# single_motor_driver_v6_patino.net
KiCad netlist of a schematic drawn in EAGLE
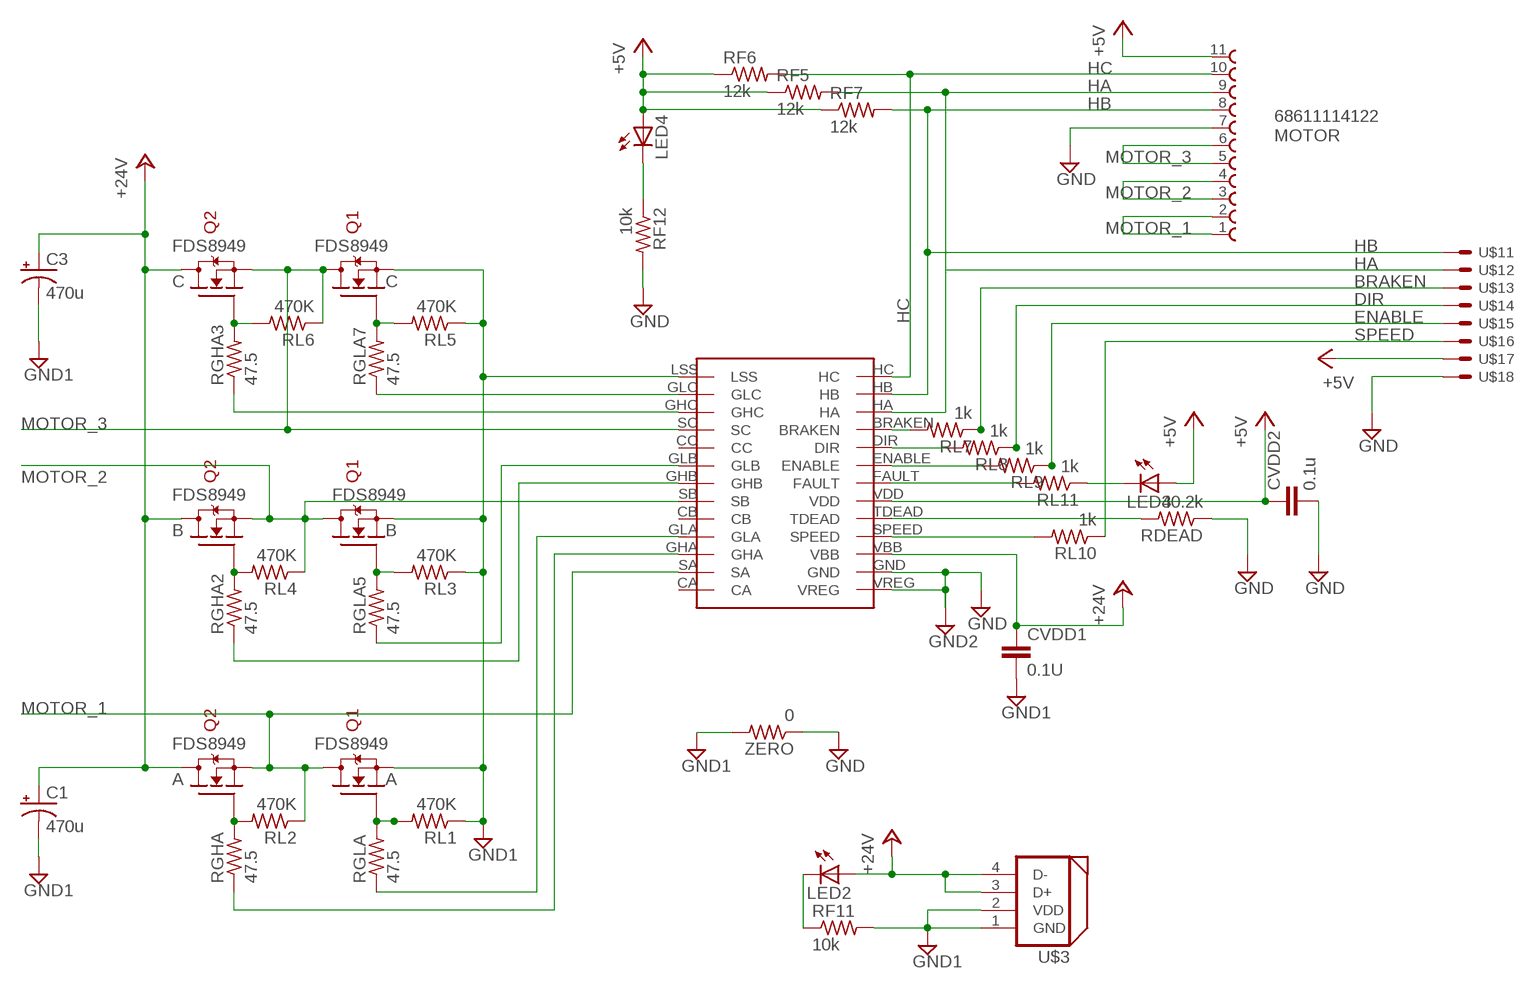
[diagram p0: schematic, sheet 1]

(export (version "E")
  (design (tool "Eeschema 10.0.6"))
  (components
    (comp (ref "A")
      (value "FDS8949")
      (footprint "eagle-import:SOIC8")
      (libsource (lib "eagle-import") (part "FDS8949"))
    )
    (comp (ref "B")
      (value "FDS8949")
      (footprint "eagle-import:SOIC8")
      (libsource (lib "eagle-import") (part "FDS8949"))
    )
    (comp (ref "C")
      (value "FDS8949")
      (footprint "eagle-import:SOIC8")
      (libsource (lib "eagle-import") (part "FDS8949"))
    )
    (comp (ref "C1")
      (value "470u")
      (footprint "eagle-import:140CLH-1010")
      (libsource (lib "eagle-import") (part "CPOL-US140CLH-1010"))
    )
    (comp (ref "C3")
      (value "470u")
      (footprint "eagle-import:140CLH-1010")
      (libsource (lib "eagle-import") (part "CPOL-US140CLH-1010"))
    )
    (comp (ref "CVDD1")
      (value "0.1U")
      (footprint "eagle-import:C0805")
      (libsource (lib "eagle-import") (part "C-EUC0805"))
    )
    (comp (ref "CVDD2")
      (value "0.1u")
      (footprint "eagle-import:C0805")
      (libsource (lib "eagle-import") (part "C-EUC0805"))
    )
    (comp (ref "LED2")
      (value "LEDCHIPLED_0805")
      (footprint "eagle-import:CHIPLED_0805")
      (libsource (lib "eagle-import") (part "LEDCHIPLED_0805"))
    )
    (comp (ref "LED3")
      (value "LEDCHIPLED_0805")
      (footprint "eagle-import:CHIPLED_0805")
      (libsource (lib "eagle-import") (part "LEDCHIPLED_0805"))
    )
    (comp (ref "LED4")
      (value "LEDCHIPLED_0805")
      (footprint "eagle-import:CHIPLED_0805")
      (libsource (lib "eagle-import") (part "LEDCHIPLED_0805"))
    )
    (comp (ref "MOTOR")
      (value "68611114122")
      (footprint "eagle-import:68611114122")
      (libsource (lib "eagle-import") (part "68611114122"))
    )
    (comp (ref "RDEAD")
      (value "40.2k")
      (footprint "eagle-import:R0805")
      (libsource (lib "eagle-import") (part "R-US_R0805"))
    )
    (comp (ref "RF5")
      (value "12k")
      (footprint "eagle-import:R0805")
      (libsource (lib "eagle-import") (part "R-US_R0805"))
    )
    (comp (ref "RF6")
      (value "12k")
      (footprint "eagle-import:R0805")
      (libsource (lib "eagle-import") (part "R-US_R0805"))
    )
    (comp (ref "RF7")
      (value "12k")
      (footprint "eagle-import:R0805")
      (libsource (lib "eagle-import") (part "R-US_R0805"))
    )
    (comp (ref "RF11")
      (value "10k")
      (footprint "eagle-import:R0805")
      (libsource (lib "eagle-import") (part "R-US_R0805"))
    )
    (comp (ref "RF12")
      (value "10k")
      (footprint "eagle-import:R0805")
      (libsource (lib "eagle-import") (part "R-US_R0805"))
    )
    (comp (ref "RGHA")
      (value "47.5")
      (footprint "eagle-import:R0805")
      (libsource (lib "eagle-import") (part "R-US_R0805"))
    )
    (comp (ref "RGHA2")
      (value "47.5")
      (footprint "eagle-import:R0805")
      (libsource (lib "eagle-import") (part "R-US_R0805"))
    )
    (comp (ref "RGHA3")
      (value "47.5")
      (footprint "eagle-import:R0805")
      (libsource (lib "eagle-import") (part "R-US_R0805"))
    )
    (comp (ref "RGLA")
      (value "47.5")
      (footprint "eagle-import:R0805")
      (libsource (lib "eagle-import") (part "R-US_R0805"))
    )
    (comp (ref "RGLA5")
      (value "47.5")
      (footprint "eagle-import:R0805")
      (libsource (lib "eagle-import") (part "R-US_R0805"))
    )
    (comp (ref "RGLA7")
      (value "47.5")
      (footprint "eagle-import:R0805")
      (libsource (lib "eagle-import") (part "R-US_R0805"))
    )
    (comp (ref "RL1")
      (value "470K")
      (footprint "eagle-import:R0805")
      (libsource (lib "eagle-import") (part "R-US_R0805"))
    )
    (comp (ref "RL2")
      (value "470K")
      (footprint "eagle-import:R0805")
      (libsource (lib "eagle-import") (part "R-US_R0805"))
    )
    (comp (ref "RL3")
      (value "470K")
      (footprint "eagle-import:R0805")
      (libsource (lib "eagle-import") (part "R-US_R0805"))
    )
    (comp (ref "RL4")
      (value "470K")
      (footprint "eagle-import:R0805")
      (libsource (lib "eagle-import") (part "R-US_R0805"))
    )
    (comp (ref "RL5")
      (value "470K")
      (footprint "eagle-import:R0805")
      (libsource (lib "eagle-import") (part "R-US_R0805"))
    )
    (comp (ref "RL6")
      (value "470K")
      (footprint "eagle-import:R0805")
      (libsource (lib "eagle-import") (part "R-US_R0805"))
    )
    (comp (ref "RL7")
      (value "1k")
      (footprint "eagle-import:R0805")
      (libsource (lib "eagle-import") (part "R-US_R0805"))
    )
    (comp (ref "RL8")
      (value "1k")
      (footprint "eagle-import:R0805")
      (libsource (lib "eagle-import") (part "R-US_R0805"))
    )
    (comp (ref "RL9")
      (value "1k")
      (footprint "eagle-import:R0805")
      (libsource (lib "eagle-import") (part "R-US_R0805"))
    )
    (comp (ref "RL10")
      (value "1k")
      (footprint "eagle-import:R0805")
      (libsource (lib "eagle-import") (part "R-US_R0805"))
    )
    (comp (ref "RL11")
      (value "1k")
      (footprint "eagle-import:R0805")
      (libsource (lib "eagle-import") (part "R-US_R0805"))
    )
    (comp (ref "U$1")
      (value "JST8")
      (footprint "eagle-import:JST")
      (libsource (lib "eagle-import") (part "JST8"))
    )
    (comp (ref "U$2")
      (value "TSSOP28-BRK")
      (footprint "eagle-import:TSSOP28-BRK")
      (libsource (lib "eagle-import") (part "TSSOP28-BRK"))
    )
    (comp (ref "U$3")
      (value "DYNAMIXEL_RS485")
      (footprint "eagle-import:DYNAMIXEL_SPOX_04")
      (libsource (lib "eagle-import") (part "DYNAMIXEL_RS485"))
    )
    (comp (ref "ZERO")
      (value "0")
      (footprint "eagle-import:R0805")
      (libsource (lib "eagle-import") (part "R-US_R0805"))
    )
  )
  (nets
    (net (code "1") (name "+5V") (class "Default")
      (node (ref "CVDD2") (pin "1") (pinfunction "1_1") (pintype "passive"))
      (node (ref "LED3") (pin "A") (pinfunction "A_A") (pintype "passive"))
      (node (ref "LED4") (pin "A") (pinfunction "A_A") (pintype "passive"))
      (node (ref "MOTOR") (pin "11") (pinfunction "11_11") (pintype "passive"))
      (node (ref "RF5") (pin "1") (pinfunction "1_1") (pintype "passive"))
      (node (ref "RF6") (pin "1") (pinfunction "1_1") (pintype "passive"))
      (node (ref "RF7") (pin "1") (pinfunction "1_1") (pintype "passive"))
      (node (ref "U$1") (pin "7") (pinfunction "S_7") (pintype "passive"))
      (node (ref "U$2") (pin "VDD") (pinfunction "VDD_VDD") (pintype "bidirectional"))
    )
    (net (code "2") (name "+24V") (class "Default")
      (node (ref "A") (pin "5") (pinfunction "D2_5") (pintype "passive"))
      (node (ref "A") (pin "6") (pinfunction "D2_6") (pintype "passive"))
      (node (ref "B") (pin "5") (pinfunction "D2_5") (pintype "passive"))
      (node (ref "B") (pin "6") (pinfunction "D2_6") (pintype "passive"))
      (node (ref "C") (pin "5") (pinfunction "D2_5") (pintype "passive"))
      (node (ref "C") (pin "6") (pinfunction "D2_6") (pintype "passive"))
      (node (ref "C1") (pin "+") (pinfunction "+_+") (pintype "passive"))
      (node (ref "C3") (pin "+") (pinfunction "+_+") (pintype "passive"))
      (node (ref "CVDD1") (pin "1") (pinfunction "1_1") (pintype "passive"))
      (node (ref "LED2") (pin "A") (pinfunction "A_A") (pintype "passive"))
      (node (ref "U$2") (pin "VBB") (pinfunction "VBB_VBB") (pintype "bidirectional"))
      (node (ref "U$3") (pin "3") (pinfunction "D+_3") (pintype "bidirectional"))
      (node (ref "U$3") (pin "4") (pinfunction "D-_4") (pintype "bidirectional"))
    )
    (net (code "3") (name "/BRAKEN") (class "Default")
      (node (ref "RL7") (pin "1") (pinfunction "1_1") (pintype "passive"))
      (node (ref "U$1") (pin "3") (pinfunction "S_3") (pintype "passive"))
    )
    (net (code "4") (name "/DIR") (class "Default")
      (node (ref "RL8") (pin "1") (pinfunction "1_1") (pintype "passive"))
      (node (ref "U$1") (pin "4") (pinfunction "S_4") (pintype "passive"))
    )
    (net (code "5") (name "/ENABLE") (class "Default")
      (node (ref "RL9") (pin "1") (pinfunction "1_1") (pintype "passive"))
      (node (ref "U$1") (pin "5") (pinfunction "S_5") (pintype "passive"))
    )
    (net (code "6") (name "/HA") (class "Default")
      (node (ref "MOTOR") (pin "9") (pinfunction "9_9") (pintype "passive"))
      (node (ref "RF5") (pin "2") (pinfunction "2_2") (pintype "passive"))
      (node (ref "U$1") (pin "2") (pinfunction "S_2") (pintype "passive"))
      (node (ref "U$2") (pin "HA") (pinfunction "HA_HA") (pintype "bidirectional"))
    )
    (net (code "7") (name "/HB") (class "Default")
      (node (ref "MOTOR") (pin "8") (pinfunction "8_8") (pintype "passive"))
      (node (ref "RF7") (pin "2") (pinfunction "2_2") (pintype "passive"))
      (node (ref "U$1") (pin "1") (pinfunction "S_1") (pintype "passive"))
      (node (ref "U$2") (pin "HB") (pinfunction "HB_HB") (pintype "bidirectional"))
    )
    (net (code "8") (name "/HC") (class "Default")
      (node (ref "MOTOR") (pin "10") (pinfunction "10_10") (pintype "passive"))
      (node (ref "RF6") (pin "2") (pinfunction "2_2") (pintype "passive"))
      (node (ref "U$2") (pin "HC") (pinfunction "HC_HC") (pintype "bidirectional"))
    )
    (net (code "9") (name "/MOTOR_1") (class "Default")
      (node (ref "A") (pin "3") (pinfunction "S2_3") (pintype "passive"))
      (node (ref "A") (pin "7") (pinfunction "D1_7") (pintype "passive"))
      (node (ref "A") (pin "8") (pinfunction "D1_8") (pintype "passive"))
      (node (ref "MOTOR") (pin "1") (pinfunction "1_1") (pintype "passive"))
      (node (ref "MOTOR") (pin "2") (pinfunction "2_2") (pintype "passive"))
      (node (ref "RL2") (pin "1") (pinfunction "1_1") (pintype "passive"))
      (node (ref "U$2") (pin "SA") (pinfunction "SA_SA") (pintype "bidirectional"))
    )
    (net (code "10") (name "/MOTOR_2") (class "Default")
      (node (ref "B") (pin "3") (pinfunction "S2_3") (pintype "passive"))
      (node (ref "B") (pin "7") (pinfunction "D1_7") (pintype "passive"))
      (node (ref "B") (pin "8") (pinfunction "D1_8") (pintype "passive"))
      (node (ref "MOTOR") (pin "3") (pinfunction "3_3") (pintype "passive"))
      (node (ref "MOTOR") (pin "4") (pinfunction "4_4") (pintype "passive"))
      (node (ref "RL4") (pin "1") (pinfunction "1_1") (pintype "passive"))
      (node (ref "U$2") (pin "SB") (pinfunction "SB_SB") (pintype "bidirectional"))
    )
    (net (code "11") (name "/MOTOR_3") (class "Default")
      (node (ref "C") (pin "3") (pinfunction "S2_3") (pintype "passive"))
      (node (ref "C") (pin "7") (pinfunction "D1_7") (pintype "passive"))
      (node (ref "C") (pin "8") (pinfunction "D1_8") (pintype "passive"))
      (node (ref "MOTOR") (pin "5") (pinfunction "5_5") (pintype "passive"))
      (node (ref "MOTOR") (pin "6") (pinfunction "6_6") (pintype "passive"))
      (node (ref "RL6") (pin "1") (pinfunction "1_1") (pintype "passive"))
      (node (ref "U$2") (pin "SC") (pinfunction "SC_SC") (pintype "bidirectional"))
    )
    (net (code "12") (name "/SPEED") (class "Default")
      (node (ref "RL10") (pin "1") (pinfunction "1_1") (pintype "passive"))
      (node (ref "U$1") (pin "6") (pinfunction "S_6") (pintype "passive"))
    )
    (net (code "13") (name "GND") (class "Default")
      (node (ref "CVDD2") (pin "2") (pinfunction "2_2") (pintype "passive"))
      (node (ref "MOTOR") (pin "7") (pinfunction "7_7") (pintype "passive"))
      (node (ref "RDEAD") (pin "1") (pinfunction "1_1") (pintype "passive"))
      (node (ref "RF12") (pin "2") (pinfunction "2_2") (pintype "passive"))
      (node (ref "U$1") (pin "8") (pinfunction "S_8") (pintype "passive"))
      (node (ref "U$2") (pin "GND") (pinfunction "GND_GND") (pintype "bidirectional"))
      (node (ref "U$2") (pin "VREG") (pinfunction "VREG_VREG") (pintype "bidirectional"))
      (node (ref "ZERO") (pin "1") (pinfunction "1_1") (pintype "passive"))
    )
    (net (code "14") (name "GND1") (class "Default")
      (node (ref "A") (pin "1") (pinfunction "S1_1") (pintype "passive"))
      (node (ref "B") (pin "1") (pinfunction "S1_1") (pintype "passive"))
      (node (ref "C") (pin "1") (pinfunction "S1_1") (pintype "passive"))
      (node (ref "C1") (pin "-") (pinfunction "-_-") (pintype "passive"))
      (node (ref "C3") (pin "-") (pinfunction "-_-") (pintype "passive"))
      (node (ref "CVDD1") (pin "2") (pinfunction "2_2") (pintype "passive"))
      (node (ref "RF11") (pin "2") (pinfunction "2_2") (pintype "passive"))
      (node (ref "RL1") (pin "1") (pinfunction "1_1") (pintype "passive"))
      (node (ref "RL3") (pin "1") (pinfunction "1_1") (pintype "passive"))
      (node (ref "RL5") (pin "1") (pinfunction "1_1") (pintype "passive"))
      (node (ref "U$2") (pin "LSS") (pinfunction "LSS_LSS") (pintype "bidirectional"))
      (node (ref "U$3") (pin "1") (pinfunction "GND_1") (pintype "power_in"))
      (node (ref "U$3") (pin "2") (pinfunction "VDD_2") (pintype "power_in"))
      (node (ref "ZERO") (pin "2") (pinfunction "2_2") (pintype "passive"))
    )
    (net (code "15") (name "Net-(A-G1)") (class "Default")
      (node (ref "A") (pin "2") (pinfunction "G1_2") (pintype "passive"))
      (node (ref "RGLA") (pin "2") (pinfunction "2_2") (pintype "passive"))
      (node (ref "RL1") (pin "2") (pinfunction "2_2") (pintype "passive"))
    )
    (net (code "16") (name "Net-(A-G2)") (class "Default")
      (node (ref "A") (pin "4") (pinfunction "G2_4") (pintype "passive"))
      (node (ref "RGHA") (pin "2") (pinfunction "2_2") (pintype "passive"))
      (node (ref "RL2") (pin "2") (pinfunction "2_2") (pintype "passive"))
    )
    (net (code "17") (name "Net-(B-G1)") (class "Default")
      (node (ref "B") (pin "2") (pinfunction "G1_2") (pintype "passive"))
      (node (ref "RGLA5") (pin "2") (pinfunction "2_2") (pintype "passive"))
      (node (ref "RL3") (pin "2") (pinfunction "2_2") (pintype "passive"))
    )
    (net (code "18") (name "Net-(B-G2)") (class "Default")
      (node (ref "B") (pin "4") (pinfunction "G2_4") (pintype "passive"))
      (node (ref "RGHA2") (pin "2") (pinfunction "2_2") (pintype "passive"))
      (node (ref "RL4") (pin "2") (pinfunction "2_2") (pintype "passive"))
    )
    (net (code "19") (name "Net-(C-G1)") (class "Default")
      (node (ref "C") (pin "2") (pinfunction "G1_2") (pintype "passive"))
      (node (ref "RGLA7") (pin "2") (pinfunction "2_2") (pintype "passive"))
      (node (ref "RL5") (pin "2") (pinfunction "2_2") (pintype "passive"))
    )
    (net (code "20") (name "Net-(C-G2)") (class "Default")
      (node (ref "C") (pin "4") (pinfunction "G2_4") (pintype "passive"))
      (node (ref "RGHA3") (pin "2") (pinfunction "2_2") (pintype "passive"))
      (node (ref "RL6") (pin "2") (pinfunction "2_2") (pintype "passive"))
    )
    (net (code "21") (name "Net-(LED2-PadC)") (class "Default")
      (node (ref "LED2") (pin "C") (pinfunction "C_C") (pintype "passive"))
      (node (ref "RF11") (pin "1") (pinfunction "1_1") (pintype "passive"))
    )
    (net (code "22") (name "Net-(LED3-PadC)") (class "Default")
      (node (ref "LED3") (pin "C") (pinfunction "C_C") (pintype "passive"))
      (node (ref "RL11") (pin "1") (pinfunction "1_1") (pintype "passive"))
    )
    (net (code "23") (name "Net-(LED4-PadC)") (class "Default")
      (node (ref "LED4") (pin "C") (pinfunction "C_C") (pintype "passive"))
      (node (ref "RF12") (pin "1") (pinfunction "1_1") (pintype "passive"))
    )
    (net (code "24") (name "Net-(RDEAD-Pad2)") (class "Default")
      (node (ref "RDEAD") (pin "2") (pinfunction "2_2") (pintype "passive"))
      (node (ref "U$2") (pin "TDEAD") (pinfunction "TDEAD_TDEAD") (pintype "bidirectional"))
    )
    (net (code "25") (name "Net-(RGHA-Pad1)") (class "Default")
      (node (ref "RGHA") (pin "1") (pinfunction "1_1") (pintype "passive"))
      (node (ref "U$2") (pin "GHA") (pinfunction "GHA_GHA") (pintype "bidirectional"))
    )
    (net (code "26") (name "Net-(RGHA2-Pad1)") (class "Default")
      (node (ref "RGHA2") (pin "1") (pinfunction "1_1") (pintype "passive"))
      (node (ref "U$2") (pin "GHB") (pinfunction "GHB_GHB") (pintype "bidirectional"))
    )
    (net (code "27") (name "Net-(RGHA3-Pad1)") (class "Default")
      (node (ref "RGHA3") (pin "1") (pinfunction "1_1") (pintype "passive"))
      (node (ref "U$2") (pin "GHC") (pinfunction "GHC_GHC") (pintype "bidirectional"))
    )
    (net (code "28") (name "Net-(RGLA-Pad1)") (class "Default")
      (node (ref "RGLA") (pin "1") (pinfunction "1_1") (pintype "passive"))
      (node (ref "U$2") (pin "GLA") (pinfunction "GLA_GLA") (pintype "bidirectional"))
    )
    (net (code "29") (name "Net-(RGLA5-Pad1)") (class "Default")
      (node (ref "RGLA5") (pin "1") (pinfunction "1_1") (pintype "passive"))
      (node (ref "U$2") (pin "GLB") (pinfunction "GLB_GLB") (pintype "bidirectional"))
    )
    (net (code "30") (name "Net-(RGLA7-Pad1)") (class "Default")
      (node (ref "RGLA7") (pin "1") (pinfunction "1_1") (pintype "passive"))
      (node (ref "U$2") (pin "GLC") (pinfunction "GLC_GLC") (pintype "bidirectional"))
    )
    (net (code "31") (name "Net-(RL7-Pad2)") (class "Default")
      (node (ref "RL7") (pin "2") (pinfunction "2_2") (pintype "passive"))
      (node (ref "U$2") (pin "BRAKEN") (pinfunction "BRAKEN_BRAKEN") (pintype "bidirectional"))
    )
    (net (code "32") (name "Net-(RL8-Pad2)") (class "Default")
      (node (ref "RL8") (pin "2") (pinfunction "2_2") (pintype "passive"))
      (node (ref "U$2") (pin "DIR") (pinfunction "DIR_DIR") (pintype "bidirectional"))
    )
    (net (code "33") (name "Net-(RL9-Pad2)") (class "Default")
      (node (ref "RL9") (pin "2") (pinfunction "2_2") (pintype "passive"))
      (node (ref "U$2") (pin "ENABLE") (pinfunction "ENABLE_ENABLE") (pintype "bidirectional"))
    )
    (net (code "34") (name "Net-(RL10-Pad2)") (class "Default")
      (node (ref "RL10") (pin "2") (pinfunction "2_2") (pintype "passive"))
      (node (ref "U$2") (pin "SPEED") (pinfunction "SPEED_SPEED") (pintype "bidirectional"))
    )
    (net (code "35") (name "Net-(RL11-Pad2)") (class "Default")
      (node (ref "RL11") (pin "2") (pinfunction "2_2") (pintype "passive"))
      (node (ref "U$2") (pin "FAULT") (pinfunction "FAULT_FAULT") (pintype "bidirectional"))
    )
    (net (code "36") (name "unconnected-(U$2-PadCA)") (class "Default")
      (node (ref "U$2") (pin "CA") (pinfunction "CA_CA") (pintype "bidirectional"))
    )
    (net (code "37") (name "unconnected-(U$2-PadCB)") (class "Default")
      (node (ref "U$2") (pin "CB") (pinfunction "CB_CB") (pintype "bidirectional"))
    )
    (net (code "38") (name "unconnected-(U$2-PadCC)") (class "Default")
      (node (ref "U$2") (pin "CC") (pinfunction "CC_CC") (pintype "bidirectional"))
    )
  )
)
